# control.net
KiCad netlist of a schematic drawn in EAGLE
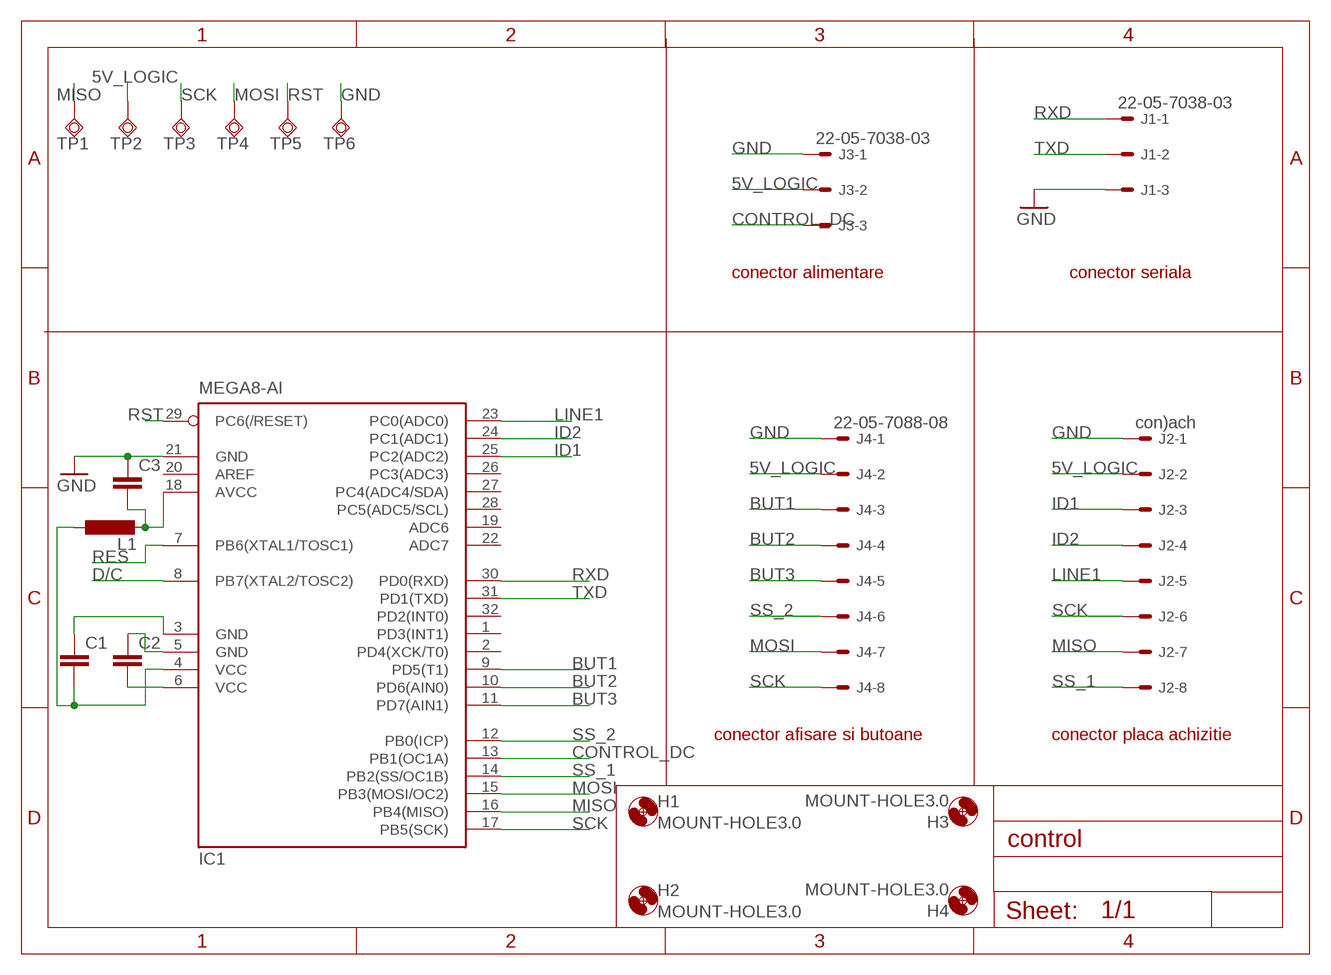
[diagram p0: schematic, sheet 1]

(export (version "E")
  (design (tool "Eeschema 10.0.6"))
  (components
    (comp (ref "C1")
      (value "C-EUC0805K")
      (footprint "eagle-import:C0805K")
      (libsource (lib "eagle-import") (part "C-EUC0805K"))
    )
    (comp (ref "C2")
      (value "C-EUC0805K")
      (footprint "eagle-import:C0805K")
      (libsource (lib "eagle-import") (part "C-EUC0805K"))
    )
    (comp (ref "C3")
      (value "C-EUC0805K")
      (footprint "eagle-import:C0805K")
      (libsource (lib "eagle-import") (part "C-EUC0805K"))
    )
    (comp (ref "H1")
      (value "MOUNT-HOLE3.0")
      (footprint "eagle-import:3,0")
      (libsource (lib "eagle-import") (part "MOUNT-HOLE3.0"))
    )
    (comp (ref "H2")
      (value "MOUNT-HOLE3.0")
      (footprint "eagle-import:3,0")
      (libsource (lib "eagle-import") (part "MOUNT-HOLE3.0"))
    )
    (comp (ref "H3")
      (value "MOUNT-HOLE3.0")
      (footprint "eagle-import:3,0")
      (libsource (lib "eagle-import") (part "MOUNT-HOLE3.0"))
    )
    (comp (ref "H4")
      (value "MOUNT-HOLE3.0")
      (footprint "eagle-import:3,0")
      (libsource (lib "eagle-import") (part "MOUNT-HOLE3.0"))
    )
    (comp (ref "IC1")
      (value "MEGA8-AI")
      (footprint "eagle-import:TQFP32-08")
      (fields (field (name "MPN") "ATMEGA8-16AU"))
      (libsource (lib "eagle-import") (part "MEGA8-AI"))
    )
    (comp (ref "J1")
      (value "22-05-7038-03")
      (footprint "eagle-import:7395-03")
      (libsource (lib "eagle-import") (part "22-?-0305-7038"))
    )
    (comp (ref "J2")
      (value "con)ach")
      (footprint "eagle-import:7395-08")
      (libsource (lib "eagle-import") (part "22-?-0805-7088"))
    )
    (comp (ref "J3")
      (value "22-05-7038-03")
      (footprint "eagle-import:7395-03")
      (libsource (lib "eagle-import") (part "22-?-0305-7038"))
    )
    (comp (ref "J4")
      (value "22-05-7088-08")
      (footprint "eagle-import:7395-08")
      (libsource (lib "eagle-import") (part "22-?-0805-7088"))
    )
    (comp (ref "L1")
      (value "L-EU0204/7")
      (footprint "eagle-import:0204_7")
      (libsource (lib "eagle-import") (part "L-EU0204/7"))
    )
    (comp (ref "TP1")
      (value "TPSQPAD1-13")
      (footprint "eagle-import:P1-13")
      (libsource (lib "eagle-import") (part "TPSQPAD1-13"))
    )
    (comp (ref "TP2")
      (value "TPSQPAD1-13")
      (footprint "eagle-import:P1-13")
      (libsource (lib "eagle-import") (part "TPSQPAD1-13"))
    )
    (comp (ref "TP3")
      (value "TPSQPAD1-13")
      (footprint "eagle-import:P1-13")
      (libsource (lib "eagle-import") (part "TPSQPAD1-13"))
    )
    (comp (ref "TP4")
      (value "TPSQPAD1-13")
      (footprint "eagle-import:P1-13")
      (libsource (lib "eagle-import") (part "TPSQPAD1-13"))
    )
    (comp (ref "TP5")
      (value "TPSQPAD1-13")
      (footprint "eagle-import:P1-13")
      (libsource (lib "eagle-import") (part "TPSQPAD1-13"))
    )
    (comp (ref "TP6")
      (value "TPSQPAD1-13")
      (footprint "eagle-import:P1-13")
      (libsource (lib "eagle-import") (part "TPSQPAD1-13"))
    )
  )
  (nets
    (net (code "1") (name "/5V_LOGIC") (class "Default")
      (node (ref "C1") (pin "2") (pinfunction "2_2") (pintype "passive"))
      (node (ref "C2") (pin "2") (pinfunction "2_2") (pintype "passive"))
      (node (ref "IC1") (pin "4") (pinfunction "VCC_4") (pintype "power_in"))
      (node (ref "IC1") (pin "6") (pinfunction "VCC_6") (pintype "power_in"))
      (node (ref "J2") (pin "2") (pinfunction "S_2") (pintype "passive"))
      (node (ref "J3") (pin "2") (pinfunction "S_2") (pintype "passive"))
      (node (ref "J4") (pin "2") (pinfunction "S_2") (pintype "passive"))
      (node (ref "L1") (pin "1") (pinfunction "1_1") (pintype "passive"))
      (node (ref "TP2") (pin "TP") (pinfunction "TP_TP") (pintype "input"))
    )
    (net (code "2") (name "/BUT1") (class "Default")
      (node (ref "IC1") (pin "9") (pinfunction "PD5(T1)_9") (pintype "bidirectional"))
      (node (ref "J4") (pin "3") (pinfunction "S_3") (pintype "passive"))
    )
    (net (code "3") (name "/BUT2") (class "Default")
      (node (ref "IC1") (pin "10") (pinfunction "PD6(AIN0)_10") (pintype "bidirectional"))
      (node (ref "J4") (pin "4") (pinfunction "S_4") (pintype "passive"))
    )
    (net (code "4") (name "/BUT3") (class "Default")
      (node (ref "IC1") (pin "11") (pinfunction "PD7(AIN1)_11") (pintype "bidirectional"))
      (node (ref "J4") (pin "5") (pinfunction "S_5") (pintype "passive"))
    )
    (net (code "5") (name "/CONTROL_DC") (class "Default")
      (node (ref "IC1") (pin "13") (pinfunction "PB1(OC1A)_13") (pintype "bidirectional"))
      (node (ref "J3") (pin "3") (pinfunction "S_3") (pintype "passive"))
    )
    (net (code "6") (name "/D{slash}C") (class "Default")
      (node (ref "IC1") (pin "8") (pinfunction "PB7(XTAL2/TOSC2)_8") (pintype "bidirectional"))
    )
    (net (code "7") (name "/ID1") (class "Default")
      (node (ref "IC1") (pin "25") (pinfunction "PC2(ADC2)_25") (pintype "bidirectional"))
      (node (ref "J2") (pin "3") (pinfunction "S_3") (pintype "passive"))
    )
    (net (code "8") (name "/ID2") (class "Default")
      (node (ref "IC1") (pin "24") (pinfunction "PC1(ADC1)_24") (pintype "bidirectional"))
      (node (ref "J2") (pin "4") (pinfunction "S_4") (pintype "passive"))
    )
    (net (code "9") (name "/LINE1") (class "Default")
      (node (ref "IC1") (pin "23") (pinfunction "PC0(ADC0)_23") (pintype "bidirectional"))
      (node (ref "J2") (pin "5") (pinfunction "S_5") (pintype "passive"))
    )
    (net (code "10") (name "/MISO") (class "Default")
      (node (ref "IC1") (pin "16") (pinfunction "PB4(MISO)_16") (pintype "bidirectional"))
      (node (ref "J2") (pin "7") (pinfunction "S_7") (pintype "passive"))
      (node (ref "TP1") (pin "TP") (pinfunction "TP_TP") (pintype "input"))
    )
    (net (code "11") (name "/MOSI") (class "Default")
      (node (ref "IC1") (pin "15") (pinfunction "PB3(MOSI/OC2)_15") (pintype "bidirectional"))
      (node (ref "J4") (pin "7") (pinfunction "S_7") (pintype "passive"))
      (node (ref "TP4") (pin "TP") (pinfunction "TP_TP") (pintype "input"))
    )
    (net (code "12") (name "/RES") (class "Default")
      (node (ref "IC1") (pin "7") (pinfunction "PB6(XTAL1/TOSC1)_7") (pintype "bidirectional"))
    )
    (net (code "13") (name "/RST") (class "Default")
      (node (ref "IC1") (pin "29") (pinfunction "PC6(/RESET)_29") (pintype "bidirectional"))
      (node (ref "TP5") (pin "TP") (pinfunction "TP_TP") (pintype "input"))
    )
    (net (code "14") (name "/RXD") (class "Default")
      (node (ref "IC1") (pin "30") (pinfunction "PD0(RXD)_30") (pintype "bidirectional"))
      (node (ref "J1") (pin "1") (pinfunction "S_1") (pintype "passive"))
    )
    (net (code "15") (name "/SCK") (class "Default")
      (node (ref "IC1") (pin "17") (pinfunction "PB5(SCK)_17") (pintype "bidirectional"))
      (node (ref "J2") (pin "6") (pinfunction "S_6") (pintype "passive"))
      (node (ref "J4") (pin "8") (pinfunction "S_8") (pintype "passive"))
      (node (ref "TP3") (pin "TP") (pinfunction "TP_TP") (pintype "input"))
    )
    (net (code "16") (name "/SS_1") (class "Default")
      (node (ref "IC1") (pin "14") (pinfunction "PB2(SS/OC1B)_14") (pintype "bidirectional"))
      (node (ref "J2") (pin "8") (pinfunction "S_8") (pintype "passive"))
    )
    (net (code "17") (name "/SS_2") (class "Default")
      (node (ref "IC1") (pin "12") (pinfunction "PB0(ICP)_12") (pintype "bidirectional"))
      (node (ref "J4") (pin "6") (pinfunction "S_6") (pintype "passive"))
    )
    (net (code "18") (name "/TXD") (class "Default")
      (node (ref "IC1") (pin "31") (pinfunction "PD1(TXD)_31") (pintype "bidirectional"))
      (node (ref "J1") (pin "2") (pinfunction "S_2") (pintype "passive"))
    )
    (net (code "19") (name "GND") (class "Default")
      (node (ref "C1") (pin "1") (pinfunction "1_1") (pintype "passive"))
      (node (ref "C2") (pin "1") (pinfunction "1_1") (pintype "passive"))
      (node (ref "C3") (pin "1") (pinfunction "1_1") (pintype "passive"))
      (node (ref "IC1") (pin "21") (pinfunction "GND_21") (pintype "power_in"))
      (node (ref "IC1") (pin "3") (pinfunction "GND_3") (pintype "power_in"))
      (node (ref "IC1") (pin "5") (pinfunction "GND_5") (pintype "power_in"))
      (node (ref "J1") (pin "3") (pinfunction "S_3") (pintype "passive"))
      (node (ref "J2") (pin "1") (pinfunction "S_1") (pintype "passive"))
      (node (ref "J3") (pin "1") (pinfunction "S_1") (pintype "passive"))
      (node (ref "J4") (pin "1") (pinfunction "S_1") (pintype "passive"))
      (node (ref "TP6") (pin "TP") (pinfunction "TP_TP") (pintype "input"))
    )
    (net (code "20") (name "Net-(IC1-AVCC)") (class "Default")
      (node (ref "C3") (pin "2") (pinfunction "2_2") (pintype "passive"))
      (node (ref "IC1") (pin "18") (pinfunction "AVCC_18") (pintype "power_in"))
      (node (ref "L1") (pin "2") (pinfunction "2_2") (pintype "passive"))
    )
    (net (code "21") (name "unconnected-(IC1-ADC6-Pad19)") (class "Default")
      (node (ref "IC1") (pin "19") (pinfunction "ADC6_19") (pintype "bidirectional"))
    )
    (net (code "22") (name "unconnected-(IC1-ADC7-Pad22)") (class "Default")
      (node (ref "IC1") (pin "22") (pinfunction "ADC7_22") (pintype "bidirectional"))
    )
    (net (code "23") (name "unconnected-(IC1-AREF-Pad20)") (class "Default")
      (node (ref "IC1") (pin "20") (pinfunction "AREF_20") (pintype "passive"))
    )
    (net (code "24") (name "unconnected-(IC1-PC3(ADC3)-Pad26)") (class "Default")
      (node (ref "IC1") (pin "26") (pinfunction "PC3(ADC3)_26") (pintype "bidirectional"))
    )
    (net (code "25") (name "unconnected-(IC1-PC4(ADC4{slash}SDA)-Pad27)") (class "Default")
      (node (ref "IC1") (pin "27") (pinfunction "PC4(ADC4/SDA)_27") (pintype "bidirectional"))
    )
    (net (code "26") (name "unconnected-(IC1-PC5(ADC5{slash}SCL)-Pad28)") (class "Default")
      (node (ref "IC1") (pin "28") (pinfunction "PC5(ADC5/SCL)_28") (pintype "bidirectional"))
    )
    (net (code "27") (name "unconnected-(IC1-PD2(INT0)-Pad32)") (class "Default")
      (node (ref "IC1") (pin "32") (pinfunction "PD2(INT0)_32") (pintype "bidirectional"))
    )
    (net (code "28") (name "unconnected-(IC1-PD3(INT1)-Pad1)") (class "Default")
      (node (ref "IC1") (pin "1") (pinfunction "PD3(INT1)_1") (pintype "bidirectional"))
    )
    (net (code "29") (name "unconnected-(IC1-PD4(XCK{slash}T0)-Pad2)") (class "Default")
      (node (ref "IC1") (pin "2") (pinfunction "PD4(XCK/T0)_2") (pintype "bidirectional"))
    )
  )
)
